# HIVE_SIGHT_TOP.net
KiCad netlist of a schematic drawn in Altium Designer
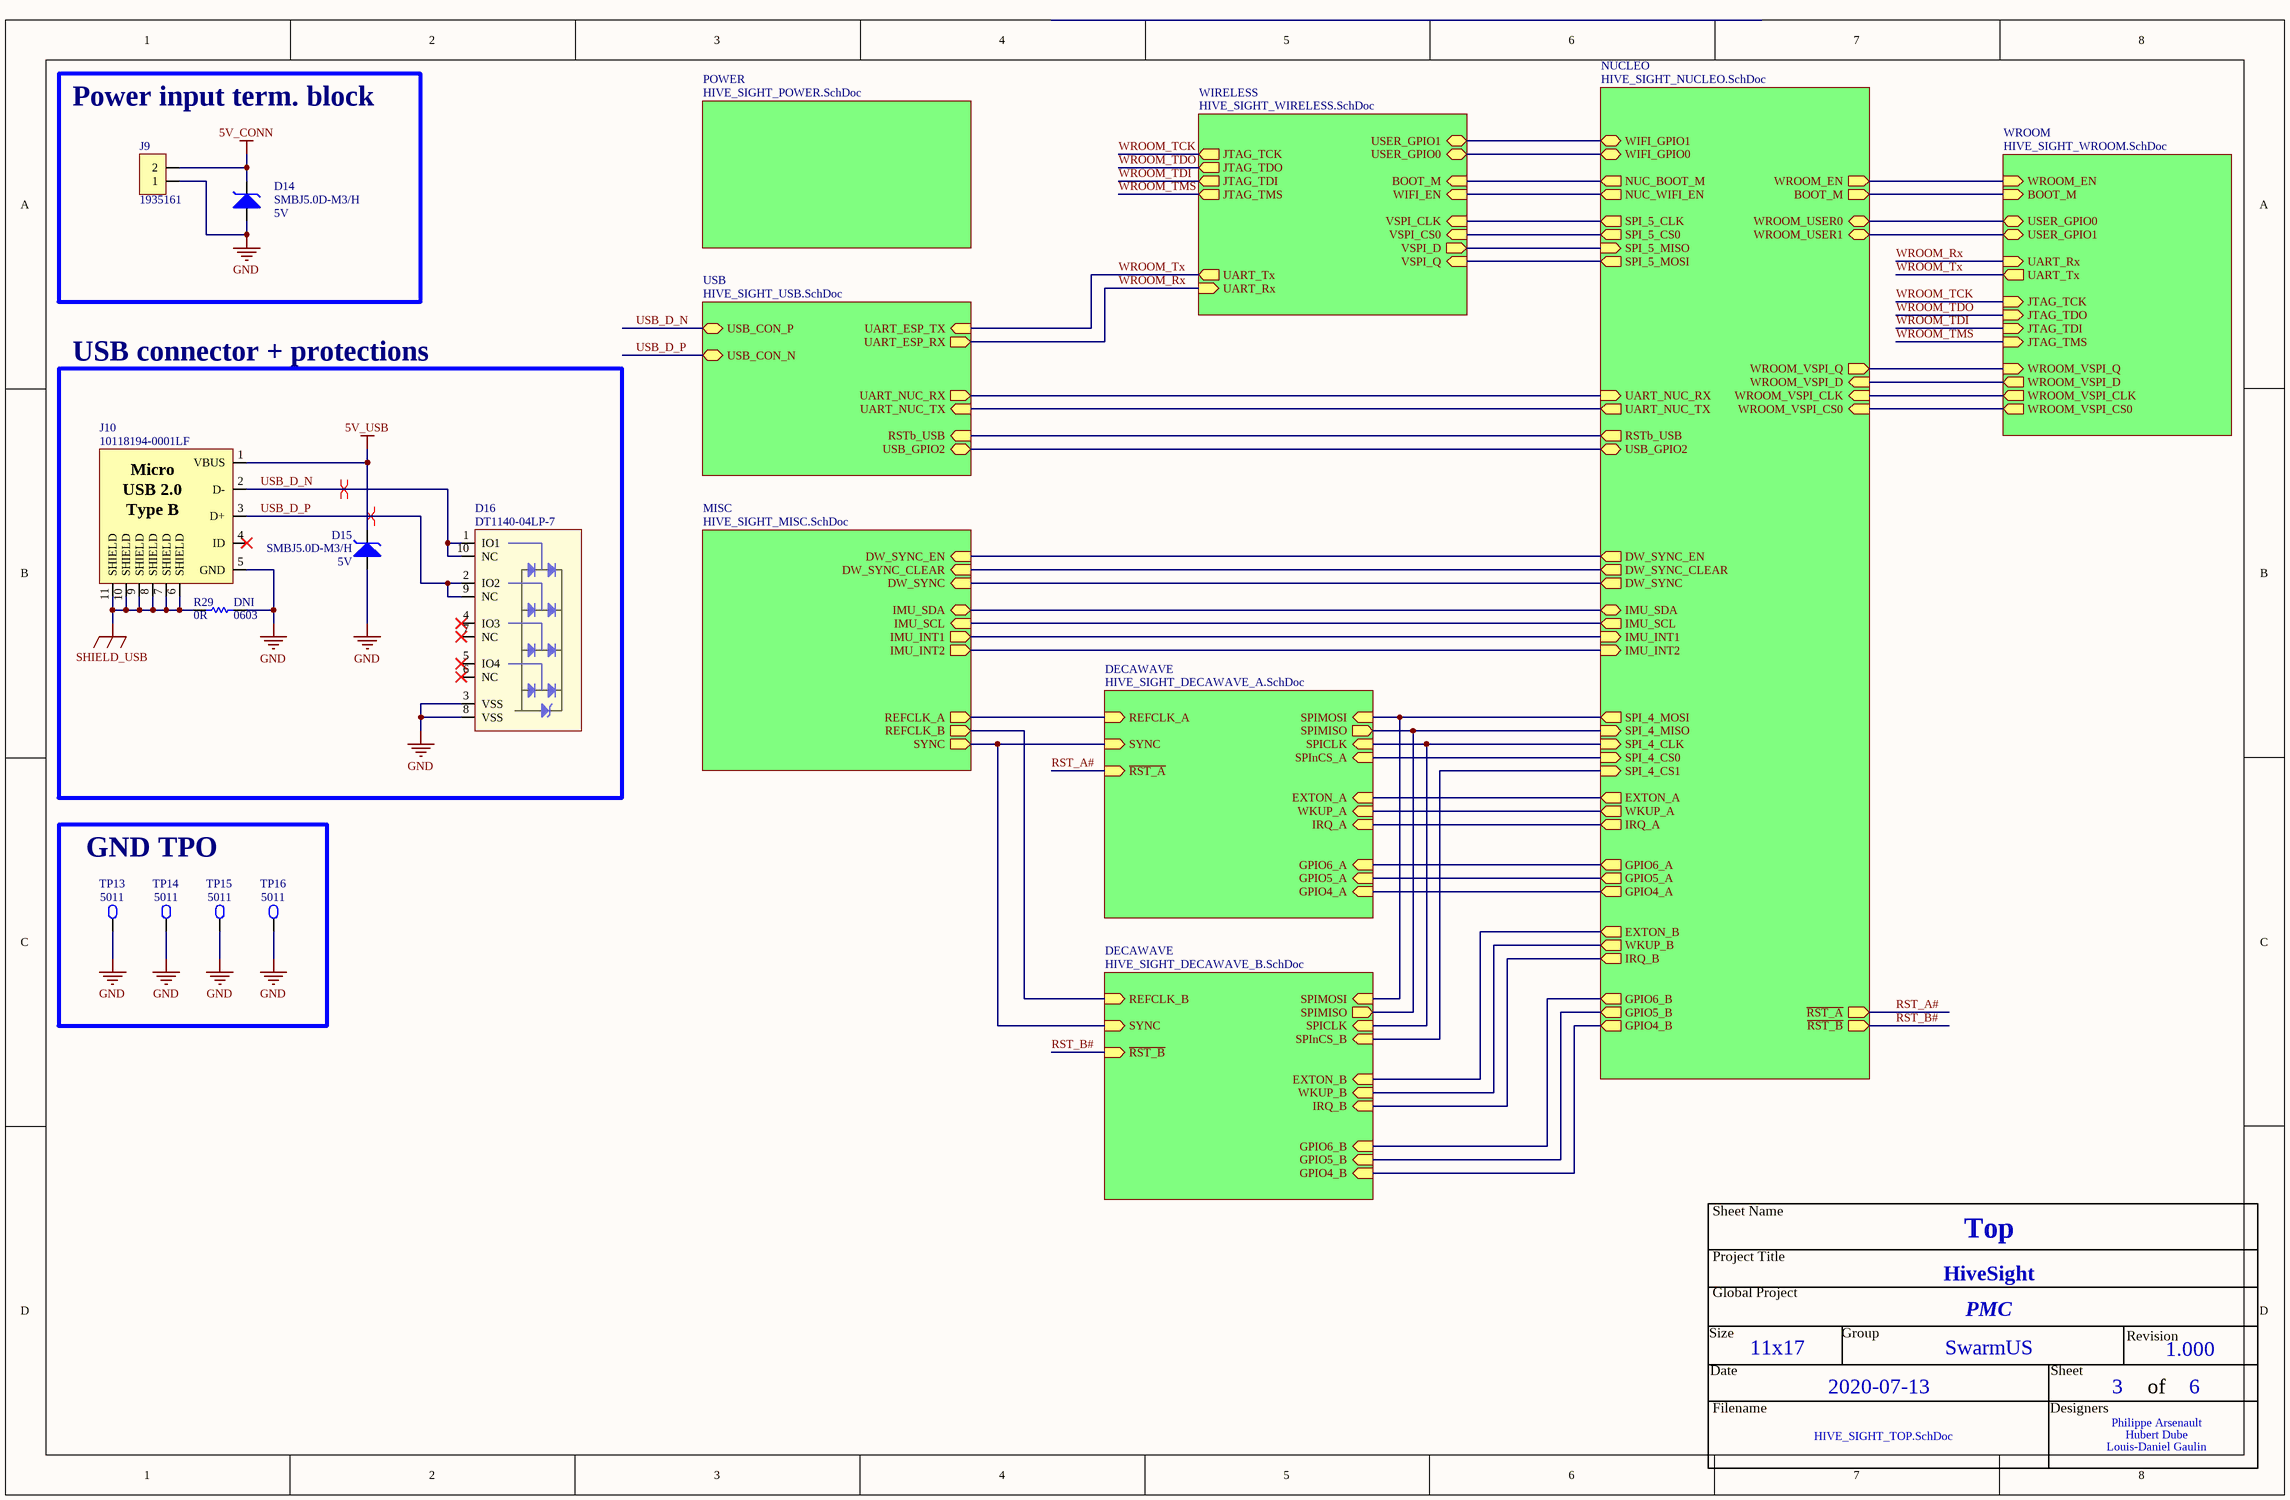
[diagram p0: HIVE_SIGHT_TOP.SchDoc]

(export (version "E")
  (design (tool "Eeschema 10.0.6"))
  (components
    (comp (ref "D14")
      (value "SMBJ5.0D-M3/H")
      (footprint "TVS_SMBJ5.0D-M3/H")
      (description "TVS - DIODE 5V 9.1V- DO-214AA")
      (fields
        (field (name "ALTIUM_VALUE") "5V")
        (field (name "CREATEDBY/DATE") "Louis-Daniel Gaulin / 27-02-2020")
        (field (name "VERIFIEDBY") "C.Paulin - 09/03/2020")
      )
      (libsource (lib "GRAMS_MASTER_LIB") (part "TVS_SMBJ5.0D-M3/H"))
    )
    (comp (ref "D15")
      (value "SMBJ5.0D-M3/H")
      (footprint "TVS_SMBJ5.0D-M3/H")
      (description "TVS - DIODE 5V 9.1V- DO-214AA")
      (fields
        (field (name "ALTIUM_VALUE") "5V")
        (field (name "CREATEDBY/DATE") "Louis-Daniel Gaulin / 27-02-2020")
        (field (name "VERIFIEDBY") "C.Paulin - 09/03/2020")
      )
      (libsource (lib "GRAMS_MASTER_LIB") (part "TVS_SMBJ5.0D-M3/H"))
    )
    (comp (ref "D16")
      (value "DT1140-04LP-7")
      (footprint "TVS_DATA_DT1140-04LP-7")
      (description "TVS - DIODE 5.5V 10V - 10-UFDFN")
      (fields
        (field (name "CREATEDBY/DATE") "Joël Lemay 2019-11-20")
        (field (name "VERIFIEDBY") "C.Paulin - 21/11/2019")
      )
      (libsource (lib "GRAMS_MASTER_LIB") (part "TVS_DATA_DT1140-04LP-7"))
    )
    (comp (ref "J9")
      (value "1935161")
      (footprint "CON_ 1935161")
      (description "CON - TERM BLK 2POS SIDE ENTRY 5MM PCB - TH - 14-26 AWG")
      (fields
        (field (name "CREATEDBY/DATE") "Louis-Daniel Gaulin / 02-11-2020")
        (field (name "VERIFIEDBY") "Philippe Arsenault/2020-11-06")
      )
      (libsource (lib "SWARMUS_LIB") (part "CON_1935161"))
    )
    (comp (ref "J10")
      (value "10118194-0001LF")
      (footprint "CON_USB_10118194-0001LF")
      (description "CON - USB MICRO B RECPT SMT R/A - 4PIN")
      (fields
        (field (name "CREATEDBY/DATE") "Arnaud Samson - 09/07/18")
        (field (name "VERIFIEDBY") "Jonathan Bouchard 2018-07-12")
      )
      (libsource (lib "GRAMS_MASTER_LIB") (part "CON_USB_10118194-0001LF"))
    )
    (comp (ref "R29")
      (value "0R")
      (footprint "RES_0603")
      (description "RES - 0 ohm jumper 1/10W - 0603")
      (fields
        (field (name "ASSEMBLY NOTE") "DNI")
        (field (name "PACKAGE") "0603")
        (field (name "Comment") "RC0603JR-070RL")
        (field (name "CREATEDBY/DATE") "L-P Gauthier 2018-10-30")
        (field (name "VERIFIEDBY") "Caroline Paulin  - 5/11/2018")
      )
      (libsource (lib "GRAMS_MASTER_LIB") (part "RES_RC0603JR-070RL"))
    )
    (comp (ref "TP13")
      (value "5011")
      (footprint "TPO_5011")
      (description "TPO - TEST POINT - TH")
      (fields
        (field (name "CREATEDBY/DATE") "Louis-Daniel Gauli / 02-11-2020")
        (field (name "VERIFIEDBY") "Philippe Arsenault/2020-11-06")
      )
      (libsource (lib "SWARMUS_LIB") (part "TPO_5011"))
    )
    (comp (ref "TP14")
      (value "5011")
      (footprint "TPO_5011")
      (description "TPO - TEST POINT - TH")
      (fields
        (field (name "CREATEDBY/DATE") "Louis-Daniel Gauli / 02-11-2020")
        (field (name "VERIFIEDBY") "Philippe Arsenault/2020-11-06")
      )
      (libsource (lib "SWARMUS_LIB") (part "TPO_5011"))
    )
    (comp (ref "TP15")
      (value "5011")
      (footprint "TPO_5011")
      (description "TPO - TEST POINT - TH")
      (fields
        (field (name "CREATEDBY/DATE") "Louis-Daniel Gauli / 02-11-2020")
        (field (name "VERIFIEDBY") "Philippe Arsenault/2020-11-06")
      )
      (libsource (lib "SWARMUS_LIB") (part "TPO_5011"))
    )
    (comp (ref "TP16")
      (value "5011")
      (footprint "TPO_5011")
      (description "TPO - TEST POINT - TH")
      (fields
        (field (name "CREATEDBY/DATE") "Louis-Daniel Gauli / 02-11-2020")
        (field (name "VERIFIEDBY") "Philippe Arsenault/2020-11-06")
      )
      (libsource (lib "SWARMUS_LIB") (part "TPO_5011"))
    )
  )
  (nets
    (net (code "37") (name "/USB_D_N") (class "Default")
      (node (ref "D16") (pin "1") (pinfunction "IO1_1") (pintype "passive"))
      (node (ref "D16") (pin "10") (pinfunction "NC_10") (pintype "passive"))
      (node (ref "J10") (pin "2") (pinfunction "D-_2") (pintype "passive"))
    )
    (net (code "38") (name "/USB_D_P") (class "Default")
      (node (ref "D16") (pin "2") (pinfunction "IO2_2") (pintype "passive"))
      (node (ref "D16") (pin "9") (pinfunction "NC_9") (pintype "passive"))
      (node (ref "J10") (pin "3") (pinfunction "D+_3") (pintype "passive"))
    )
    (net (code "58") (name "5V_CONN") (class "Default")
      (node (ref "D14") (pin "2") (pinfunction "K_2") (pintype "passive"))
      (node (ref "J9") (pin "2") (pinfunction "2_2") (pintype "passive"))
    )
    (net (code "59") (name "5V_USB") (class "Default")
      (node (ref "D15") (pin "2") (pinfunction "K_2") (pintype "passive"))
      (node (ref "J10") (pin "1") (pinfunction "VBUS_1") (pintype "passive"))
    )
    (net (code "60") (name "GND") (class "Default")
      (node (ref "D14") (pin "1") (pinfunction "A_1") (pintype "passive"))
      (node (ref "D15") (pin "1") (pinfunction "A_1") (pintype "passive"))
      (node (ref "D16") (pin "3") (pinfunction "VSS_3") (pintype "passive"))
      (node (ref "D16") (pin "8") (pinfunction "VSS_8") (pintype "passive"))
      (node (ref "J10") (pin "5") (pinfunction "GND_5") (pintype "passive"))
      (node (ref "J9") (pin "1") (pinfunction "1_1") (pintype "passive"))
      (node (ref "R29") (pin "1") (pinfunction "1_1") (pintype "passive"))
      (node (ref "TP13") (pin "1") (pinfunction "1_1") (pintype "passive"))
      (node (ref "TP14") (pin "1") (pinfunction "1_1") (pintype "passive"))
      (node (ref "TP15") (pin "1") (pinfunction "1_1") (pintype "passive"))
      (node (ref "TP16") (pin "1") (pinfunction "1_1") (pintype "passive"))
    )
    (net (code "61") (name "SHIELD_USB") (class "Default")
      (node (ref "J10") (pin "10") (pinfunction "SHIELD_10") (pintype "passive"))
      (node (ref "J10") (pin "11") (pinfunction "SHIELD_11") (pintype "passive"))
      (node (ref "J10") (pin "6") (pinfunction "SHIELD_6") (pintype "passive"))
      (node (ref "J10") (pin "7") (pinfunction "SHIELD_7") (pintype "passive"))
      (node (ref "J10") (pin "8") (pinfunction "SHIELD_8") (pintype "passive"))
      (node (ref "J10") (pin "9") (pinfunction "SHIELD_9") (pintype "passive"))
      (node (ref "R29") (pin "2") (pinfunction "2_2") (pintype "passive"))
    )
    (net (code "62") (name "unconnected-(D16-IO3-Pad4)") (class "Default")
      (node (ref "D16") (pin "4") (pinfunction "IO3_4") (pintype "passive+no_connect"))
    )
    (net (code "63") (name "unconnected-(D16-IO4-Pad5)") (class "Default")
      (node (ref "D16") (pin "5") (pinfunction "IO4_5") (pintype "passive+no_connect"))
    )
    (net (code "64") (name "unconnected-(D16-NC-Pad6)") (class "Default")
      (node (ref "D16") (pin "6") (pinfunction "NC_6") (pintype "passive+no_connect"))
    )
    (net (code "65") (name "unconnected-(D16-NC-Pad7)") (class "Default")
      (node (ref "D16") (pin "7") (pinfunction "NC_7") (pintype "passive+no_connect"))
    )
    (net (code "66") (name "unconnected-(J10-ID-Pad4)") (class "Default")
      (node (ref "J10") (pin "4") (pinfunction "ID_4") (pintype "passive+no_connect"))
    )
  )
)
